# MB1296-Power.net
KiCad netlist of a schematic drawn in Altium Designer
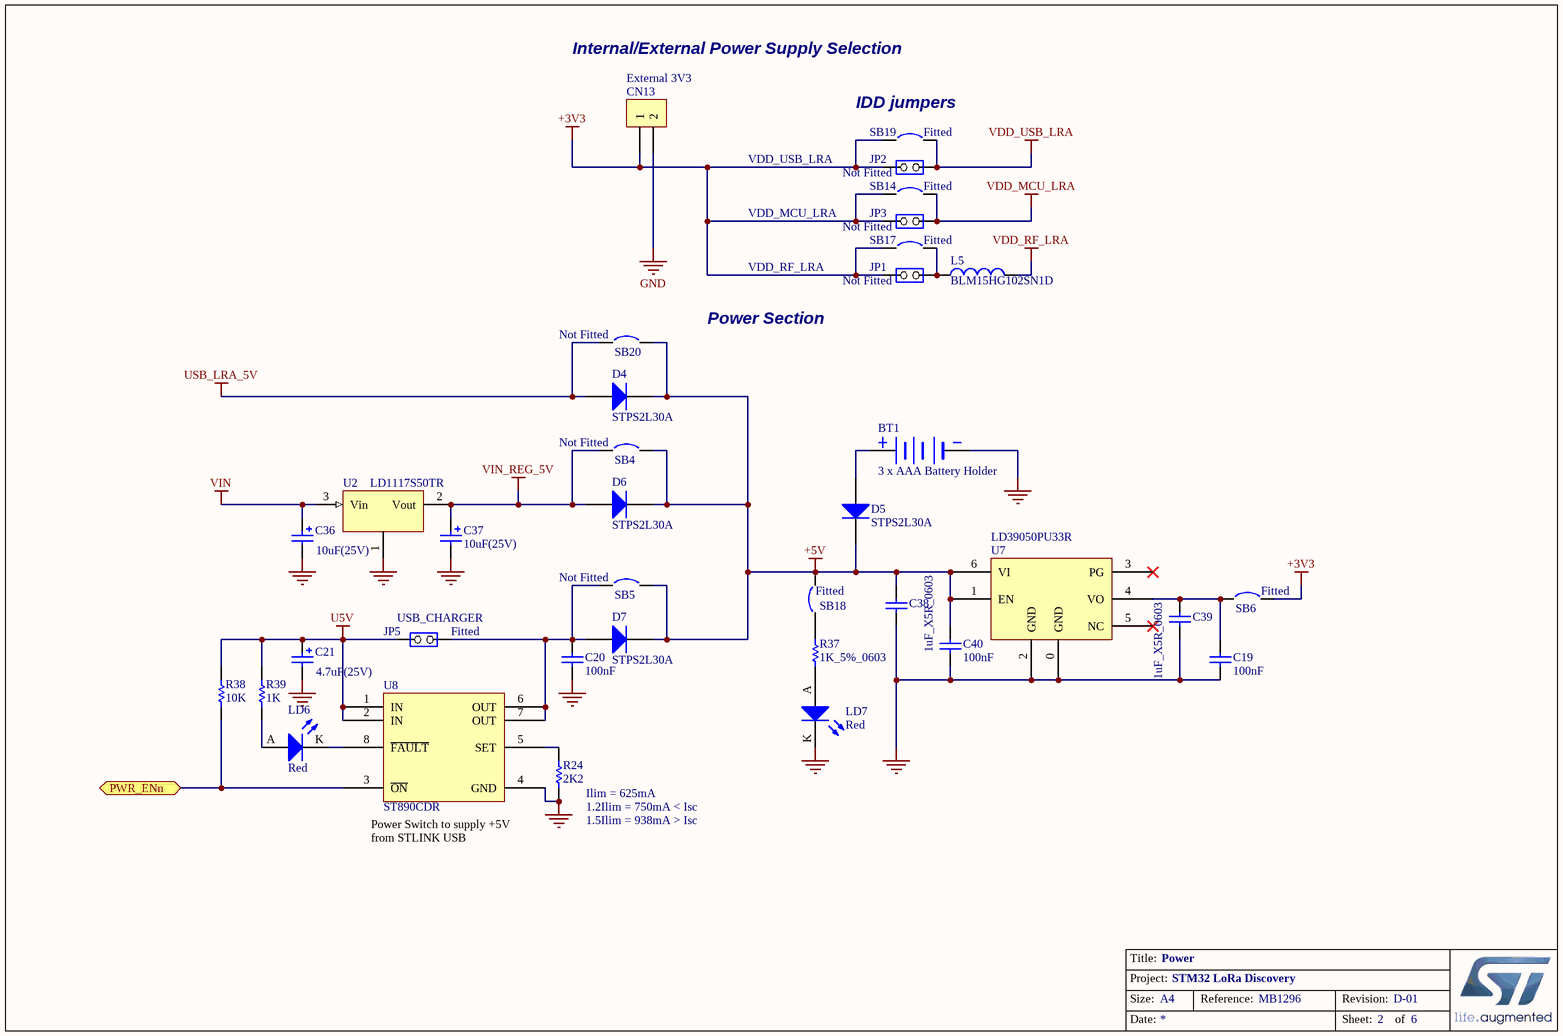
[diagram p0: MB1296-Power.SchDoc]

(export (version "E")
  (design (tool "Eeschema 10.0.6"))
  (components
    (comp (ref "BT1")
      (value "3 x AAA Battery Holder")
      (footprint "3 X AAA Battery Holder")
      (fields (field (name "MANUFACTURER") "Keystone"))
      (libsource (lib "MCD16-033-STM32_LRA_Eval_Board_1") (part "3 x AAA Battery Holder"))
    )
    (comp (ref "C19")
      (value "100nF")
      (footprint "0603C")
      (description "Capacitor 100nF")
      (fields (field (name "MANUFACTURER") "YAGEO") (field (name "PROVIDED BY") "Subcon"))
      (libsource (lib "MCD16-033-STM32_LRA_Eval_Board_1") (part "CAP"))
    )
    (comp (ref "C20")
      (value "100nF")
      (footprint "0603C")
      (description "Capacitor 100nF")
      (fields (field (name "MANUFACTURER") "YAGEO") (field (name "PROVIDED BY") "Subcon"))
      (libsource (lib "MCD16-033-STM32_LRA_Eval_Board_1") (part "CAP"))
    )
    (comp (ref "C21")
      (value "4.7uF(25V)")
      (footprint "TAN-B")
      (description "Polarized Capacitor (Radial)")
      (fields (field (name "MANUFACTURER") "YAGEO") (field (name "PROVIDED BY") "Subcon"))
      (libsource (lib "MCD16-033-STM32_LRA_Eval_Board_1") (part "Cap Pol1"))
    )
    (comp (ref "C36")
      (value "10uF(25V)")
      (footprint "TAN-B")
      (description "Polarized Capacitor (Radial)")
      (fields (field (name "MANUFACTURER") "AVX") (field (name "PROVIDED BY") "Subcon"))
      (libsource (lib "MCD16-033-STM32_LRA_Eval_Board_1") (part "Cap Pol1"))
    )
    (comp (ref "C37")
      (value "10uF(25V)")
      (footprint "TAN-B")
      (description "Polarized Capacitor (Radial)")
      (fields (field (name "MANUFACTURER") "AVX") (field (name "PROVIDED BY") "Subcon"))
      (libsource (lib "MCD16-033-STM32_LRA_Eval_Board_1") (part "Cap Pol1"))
    )
    (comp (ref "C38")
      (value "1uF_X5R_0603")
      (footprint "0603C")
      (description "0603  X5R 1µF")
      (fields (field (name "MANUFACTURER") "YAGEO") (field (name "PROVIDED BY") "Subcon"))
      (libsource (lib "MCD16-033-STM32_LRA_Eval_Board_1") (part "CAP SMD 0603  X5R 1µF 25V 10%"))
    )
    (comp (ref "C39")
      (value "1uF_X5R_0603")
      (footprint "0603C")
      (description "0603  X5R 1µF")
      (fields (field (name "MANUFACTURER") "YAGEO") (field (name "PROVIDED BY") "Subcon"))
      (libsource (lib "MCD16-033-STM32_LRA_Eval_Board_1") (part "CAP SMD 0603  X5R 1µF 25V 10%"))
    )
    (comp (ref "C40")
      (value "100nF")
      (footprint "0603C")
      (description "Capacitor 100nF")
      (fields (field (name "MANUFACTURER") "YAGEO") (field (name "PROVIDED BY") "Subcon"))
      (libsource (lib "MCD16-033-STM32_LRA_Eval_Board_1") (part "CAP"))
    )
    (comp (ref "CN13")
      (value "External 3V3")
      (footprint "SIP2")
      (description "Header 2")
      (fields (field (name "MANUFACTURER") "Kontek") (field (name "PROVIDED BY") "Subcon"))
      (libsource (lib "MCD16-033-STM32_LRA_Eval_Board_1") (part "Header 2"))
    )
    (comp (ref "D4")
      (value "STPS2L30A")
      (footprint "SMA")
      (fields (field (name "PROVIDED BY") "STM"))
      (libsource (lib "MCD16-033-STM32_LRA_Eval_Board_1") (part "STPS2L30A"))
    )
    (comp (ref "D5")
      (value "STPS2L30A")
      (footprint "SMA")
      (fields (field (name "PROVIDED BY") "STM"))
      (libsource (lib "MCD16-033-STM32_LRA_Eval_Board_1") (part "STPS2L30A"))
    )
    (comp (ref "D6")
      (value "STPS2L30A")
      (footprint "SMA")
      (fields (field (name "PROVIDED BY") "STM"))
      (libsource (lib "MCD16-033-STM32_LRA_Eval_Board_1") (part "STPS2L30A"))
    )
    (comp (ref "D7")
      (value "STPS2L30A")
      (footprint "SMA")
      (fields (field (name "PROVIDED BY") "STM"))
      (libsource (lib "MCD16-033-STM32_LRA_Eval_Board_1") (part "STPS2L30A"))
    )
    (comp (ref "JP1")
      (value "VDD_RF_LRA")
      (footprint "SIP2/2.54")
      (fields (field (name "MANUFACTURER") "Lyconn") (field (name "PROVIDED BY") "Subcon"))
      (libsource (lib "MCD16-033-STM32_LRA_Eval_Board_1") (part "JP2"))
    )
    (comp (ref "JP2")
      (value "VDD_USB_LRA")
      (footprint "SIP2/2.54")
      (fields (field (name "MANUFACTURER") "Lyconn") (field (name "PROVIDED BY") "Subcon"))
      (libsource (lib "MCD16-033-STM32_LRA_Eval_Board_1") (part "JP2"))
    )
    (comp (ref "JP3")
      (value "VDD_MCU_LRA")
      (footprint "SIP2/2.54")
      (fields (field (name "MANUFACTURER") "Lyconn") (field (name "PROVIDED BY") "Subcon"))
      (libsource (lib "MCD16-033-STM32_LRA_Eval_Board_1") (part "JP2"))
    )
    (comp (ref "JP5")
      (value "USB_CHARGER")
      (footprint "SIP2/2.54")
      (fields (field (name "MANUFACTURER") "Lyconn") (field (name "PROVIDED BY") "Subcon"))
      (libsource (lib "MCD16-033-STM32_LRA_Eval_Board_1") (part "JP2"))
    )
    (comp (ref "L5")
      (value "BLM15HG102SN1D")
      (footprint "0402")
      (fields (field (name "MANUFACTURER") "Murata Electronics"))
      (libsource (lib "MCD16-033-STM32_LRA_Eval_Board_1") (part "BLM15HG102SN1D"))
    )
    (comp (ref "LD6")
      (value "Red")
      (footprint "0603D")
      (description "Typical RED, GREEN, YELLOW, AMBER GaAs LED")
      (fields (field (name "MANUFACTURER") "Everlight"))
      (libsource (lib "MB1296-STM32_LRA_Disco") (part "LED2"))
    )
    (comp (ref "LD7")
      (value "Red")
      (footprint "0603D")
      (description "Typical RED, GREEN, YELLOW, AMBER GaAs LED")
      (fields (field (name "MANUFACTURER") "Everlight"))
      (libsource (lib "MB1296-STM32_LRA_Disco") (part "LED2"))
    )
    (comp (ref "R24")
      (value "2K2")
      (footprint "0603R")
      (description "Resistor")
      (fields (field (name "MANUFACTURER") "YAGEO") (field (name "PROVIDED BY") "Subcon"))
      (libsource (lib "MCD16-033-STM32_LRA_Eval_Board_1") (part "Res1_2"))
    )
    (comp (ref "R37")
      (value "1K_5%_0603")
      (footprint "0603")
      (description "0603 1K 50V 5% 0.063W")
      (fields (field (name "MANUFACTURER") "YAGEO") (field (name "PROVIDED BY") "Subcon"))
      (libsource (lib "MCD16-033-STM32_LRA_Eval_Board_1") (part "RES SMD 0603 1K 50V 5% 0.063W"))
    )
    (comp (ref "R38")
      (value "10K")
      (footprint "0603R")
      (description "Resistor 0603")
      (fields (field (name "MANUFACTURER") "YAGEO") (field (name "PROVIDED BY") "Subcon"))
      (libsource (lib "MCD16-033-STM32_LRA_Eval_Board_1") (part "Resistor_ST"))
    )
    (comp (ref "R39")
      (value "1K")
      (footprint "0603R")
      (description "Resistor 0603")
      (fields (field (name "MANUFACTURER") "YAGEO") (field (name "PROVIDED BY") "Subcon"))
      (libsource (lib "MCD16-033-STM32_LRA_Eval_Board_1") (part "Resistor_ST"))
    )
    (comp (ref "SB4")
      (value "Circuit Breaker")
      (footprint "JP2_SMD")
      (libsource (lib "MCD16-033-STM32_LRA_Eval_Board_1") (part "Circuit Breaker"))
    )
    (comp (ref "SB5")
      (value "Circuit Breaker")
      (footprint "JP2_SMD")
      (libsource (lib "MCD16-033-STM32_LRA_Eval_Board_1") (part "Circuit Breaker"))
    )
    (comp (ref "SB6")
      (value "Circuit Breaker")
      (footprint "JP2_SMD")
      (libsource (lib "MCD16-033-STM32_LRA_Eval_Board_1") (part "Circuit Breaker"))
    )
    (comp (ref "SB14")
      (value "Circuit Breaker")
      (footprint "JP2_SMD")
      (libsource (lib "MCD16-033-STM32_LRA_Eval_Board_1") (part "Circuit Breaker"))
    )
    (comp (ref "SB17")
      (value "Circuit Breaker")
      (footprint "JP2_SMD")
      (libsource (lib "MCD16-033-STM32_LRA_Eval_Board_1") (part "Circuit Breaker"))
    )
    (comp (ref "SB18")
      (value "Circuit Breaker")
      (footprint "JP2_SMD")
      (libsource (lib "MCD16-033-STM32_LRA_Eval_Board_1") (part "Circuit Breaker"))
    )
    (comp (ref "SB19")
      (value "Circuit Breaker")
      (footprint "JP2_SMD")
      (libsource (lib "MCD16-033-STM32_LRA_Eval_Board_1") (part "Circuit Breaker"))
    )
    (comp (ref "SB20")
      (value "Circuit Breaker")
      (footprint "JP2_SMD")
      (libsource (lib "MCD16-033-STM32_LRA_Eval_Board_1") (part "Circuit Breaker"))
    )
    (comp (ref "U2")
      (value "LD1117S50TR")
      (footprint "SOT-223")
      (fields (field (name "MANUFACTURER") "ST") (field (name "PROVIDED BY") "STM"))
      (libsource (lib "MCD16-033-STM32_LRA_Eval_Board") (part "LD1117"))
    )
    (comp (ref "U7")
      (value "LD39050PU33R")
      (footprint "DFN6(3X3)")
      (fields (field (name "MANUFACTURER") "ST") (field (name "PROVIDED BY") "STM"))
      (libsource (lib "MCD16-033-STM32_LRA_Eval_Board_1") (part "LD39050P"))
    )
    (comp (ref "U8")
      (value "ST890CDR")
      (footprint "SOIC8_1R27_4R9X6")
      (fields (field (name "MANUFACTURER") "ST") (field (name "PROVIDED BY") "STM"))
      (libsource (lib "MB1137") (part "ST890CDR"))
    )
  )
  (nets
    (net (code "1") (name "+3V3") (class "Default")
      (node (ref "CN13") (pin "1") (pinfunction "1_1") (pintype "passive"))
      (node (ref "JP1") (pin "2") (pinfunction "NO_2") (pintype "passive"))
      (node (ref "JP2") (pin "2") (pinfunction "NO_2") (pintype "passive"))
      (node (ref "JP3") (pin "2") (pinfunction "NO_2") (pintype "passive"))
      (node (ref "SB14") (pin "1") (pinfunction "1_1") (pintype "passive"))
      (node (ref "SB17") (pin "1") (pinfunction "1_1") (pintype "passive"))
      (node (ref "SB19") (pin "1") (pinfunction "1_1") (pintype "passive"))
      (node (ref "SB6") (pin "2") (pinfunction "2_2") (pintype "passive"))
    )
    (net (code "2") (name "+5V") (class "Default")
      (node (ref "C38") (pin "2") (pinfunction "2_2") (pintype "passive"))
      (node (ref "C40") (pin "2") (pinfunction "2_2") (pintype "passive"))
      (node (ref "D4") (pin "2") (pinfunction "K_2") (pintype "passive"))
      (node (ref "D5") (pin "2") (pinfunction "K_2") (pintype "passive"))
      (node (ref "D6") (pin "2") (pinfunction "K_2") (pintype "passive"))
      (node (ref "D7") (pin "2") (pinfunction "K_2") (pintype "passive"))
      (node (ref "SB18") (pin "2") (pinfunction "2_2") (pintype "passive"))
      (node (ref "SB20") (pin "2") (pinfunction "2_2") (pintype "passive"))
      (node (ref "SB4") (pin "2") (pinfunction "2_2") (pintype "passive"))
      (node (ref "SB5") (pin "2") (pinfunction "2_2") (pintype "passive"))
      (node (ref "U7") (pin "1") (pinfunction "EN_1") (pintype "passive"))
      (node (ref "U7") (pin "6") (pinfunction "VI_6") (pintype "passive"))
    )
    (net (code "3") (name "/PWR_ENn") (class "Default")
      (node (ref "R38") (pin "1") (pinfunction "1_1") (pintype "passive"))
      (node (ref "U8") (pin "3") (pinfunction "~{ON}_3") (pintype "passive"))
    )
    (net (code "4") (name "GND") (class "Default")
      (node (ref "BT1") (pin "2") (pinfunction "-_2") (pintype "passive"))
      (node (ref "C19") (pin "1") (pinfunction "1_1") (pintype "passive"))
      (node (ref "C20") (pin "1") (pinfunction "1_1") (pintype "passive"))
      (node (ref "C21") (pin "2") (pinfunction "2_2") (pintype "passive"))
      (node (ref "C36") (pin "2") (pinfunction "2_2") (pintype "passive"))
      (node (ref "C37") (pin "2") (pinfunction "2_2") (pintype "passive"))
      (node (ref "C38") (pin "1") (pinfunction "1_1") (pintype "passive"))
      (node (ref "C39") (pin "1") (pinfunction "1_1") (pintype "passive"))
      (node (ref "C40") (pin "1") (pinfunction "1_1") (pintype "passive"))
      (node (ref "CN13") (pin "2") (pinfunction "2_2") (pintype "passive"))
      (node (ref "LD7") (pin "K") (pinfunction "K_K") (pintype "passive"))
      (node (ref "R24") (pin "2") (pinfunction "2_2") (pintype "passive"))
      (node (ref "U2") (pin "1") (pintype "passive"))
      (node (ref "U7") (pin "0") (pinfunction "GND_0") (pintype "passive"))
      (node (ref "U7") (pin "2") (pinfunction "GND_2") (pintype "passive"))
      (node (ref "U8") (pin "4") (pinfunction "GND_4") (pintype "passive"))
    )
    (net (code "5") (name "Net-(BT1-+)") (class "Default")
      (node (ref "BT1") (pin "1") (pinfunction "+_1") (pintype "passive"))
      (node (ref "D5") (pin "1") (pinfunction "A_1") (pintype "passive"))
    )
    (net (code "6") (name "Net-(D7-A)") (class "Default")
      (node (ref "C20") (pin "2") (pinfunction "2_2") (pintype "passive"))
      (node (ref "D7") (pin "1") (pinfunction "A_1") (pintype "passive"))
      (node (ref "JP5") (pin "1") (pinfunction "COMMON_1") (pintype "passive"))
      (node (ref "SB5") (pin "1") (pinfunction "1_1") (pintype "passive"))
      (node (ref "U8") (pin "6") (pinfunction "OUT_6") (pintype "passive"))
      (node (ref "U8") (pin "7") (pinfunction "OUT_7") (pintype "passive"))
    )
    (net (code "7") (name "Net-(JP1-COMMON)") (class "Default")
      (node (ref "JP1") (pin "1") (pinfunction "COMMON_1") (pintype "passive"))
      (node (ref "L5") (pin "1") (pinfunction "1_1") (pintype "passive"))
      (node (ref "SB17") (pin "2") (pinfunction "2_2") (pintype "passive"))
    )
    (net (code "8") (name "Net-(LD6-PadA)") (class "Default")
      (node (ref "LD6") (pin "A") (pinfunction "A_A") (pintype "passive"))
      (node (ref "R39") (pin "1") (pinfunction "1_1") (pintype "passive"))
    )
    (net (code "9") (name "Net-(LD7-PadA)") (class "Default")
      (node (ref "LD7") (pin "A") (pinfunction "A_A") (pintype "passive"))
      (node (ref "R37") (pin "1") (pinfunction "1_1") (pintype "passive"))
    )
    (net (code "10") (name "Net-(R37-Pad2)") (class "Default")
      (node (ref "R37") (pin "2") (pinfunction "2_2") (pintype "passive"))
      (node (ref "SB18") (pin "1") (pinfunction "1_1") (pintype "passive"))
    )
    (net (code "11") (name "Net-(U7-VO)") (class "Default")
      (node (ref "C19") (pin "2") (pinfunction "2_2") (pintype "passive"))
      (node (ref "C39") (pin "2") (pinfunction "2_2") (pintype "passive"))
      (node (ref "SB6") (pin "1") (pinfunction "1_1") (pintype "passive"))
      (node (ref "U7") (pin "4") (pinfunction "VO_4") (pintype "passive"))
    )
    (net (code "12") (name "Net-(U8-SET)") (class "Default")
      (node (ref "R24") (pin "1") (pinfunction "1_1") (pintype "passive"))
      (node (ref "U8") (pin "5") (pinfunction "SET_5") (pintype "passive"))
    )
    (net (code "13") (name "Net-(U8-~{FAULT})") (class "Default")
      (node (ref "LD6") (pin "K") (pinfunction "K_K") (pintype "passive"))
      (node (ref "U8") (pin "8") (pinfunction "~{FAULT}_8") (pintype "passive"))
    )
    (net (code "14") (name "U5V") (class "Default")
      (node (ref "C21") (pin "1") (pinfunction "1_1") (pintype "passive"))
      (node (ref "JP5") (pin "2") (pinfunction "NO_2") (pintype "passive"))
      (node (ref "R38") (pin "2") (pinfunction "2_2") (pintype "passive"))
      (node (ref "R39") (pin "2") (pinfunction "2_2") (pintype "passive"))
      (node (ref "U8") (pin "1") (pinfunction "IN_1") (pintype "passive"))
      (node (ref "U8") (pin "2") (pinfunction "IN_2") (pintype "passive"))
    )
    (net (code "15") (name "USB_LRA_5V") (class "Default")
      (node (ref "D4") (pin "1") (pinfunction "A_1") (pintype "passive"))
      (node (ref "SB20") (pin "1") (pinfunction "1_1") (pintype "passive"))
    )
    (net (code "16") (name "VDD_MCU_LRA") (class "Default")
      (node (ref "JP3") (pin "1") (pinfunction "COMMON_1") (pintype "passive"))
      (node (ref "SB14") (pin "2") (pinfunction "2_2") (pintype "passive"))
    )
    (net (code "17") (name "VDD_RF_LRA") (class "Default")
      (node (ref "L5") (pin "2") (pinfunction "2_2") (pintype "passive"))
    )
    (net (code "18") (name "VDD_USB_LRA") (class "Default")
      (node (ref "JP2") (pin "1") (pinfunction "COMMON_1") (pintype "passive"))
      (node (ref "SB19") (pin "2") (pinfunction "2_2") (pintype "passive"))
    )
    (net (code "19") (name "VIN") (class "Default")
      (node (ref "C36") (pin "1") (pinfunction "1_1") (pintype "passive"))
      (node (ref "U2") (pin "3") (pinfunction "Vin_3") (pintype "input"))
    )
    (net (code "20") (name "VIN_REG_5V") (class "Default")
      (node (ref "C37") (pin "1") (pinfunction "1_1") (pintype "passive"))
      (node (ref "D6") (pin "1") (pinfunction "A_1") (pintype "passive"))
      (node (ref "SB4") (pin "1") (pinfunction "1_1") (pintype "passive"))
      (node (ref "U2") (pin "2") (pinfunction "Vout_2") (pintype "power_in"))
    )
    (net (code "21") (name "unconnected-(U7-NC-Pad5)") (class "Default")
      (node (ref "U7") (pin "5") (pinfunction "NC_5") (pintype "passive+no_connect"))
    )
    (net (code "22") (name "unconnected-(U7-PG-Pad3)") (class "Default")
      (node (ref "U7") (pin "3") (pinfunction "PG_3") (pintype "passive+no_connect"))
    )
  )
)
